# ReptileHeatMat-V1.net
KiCad netlist of a schematic drawn in EAGLE
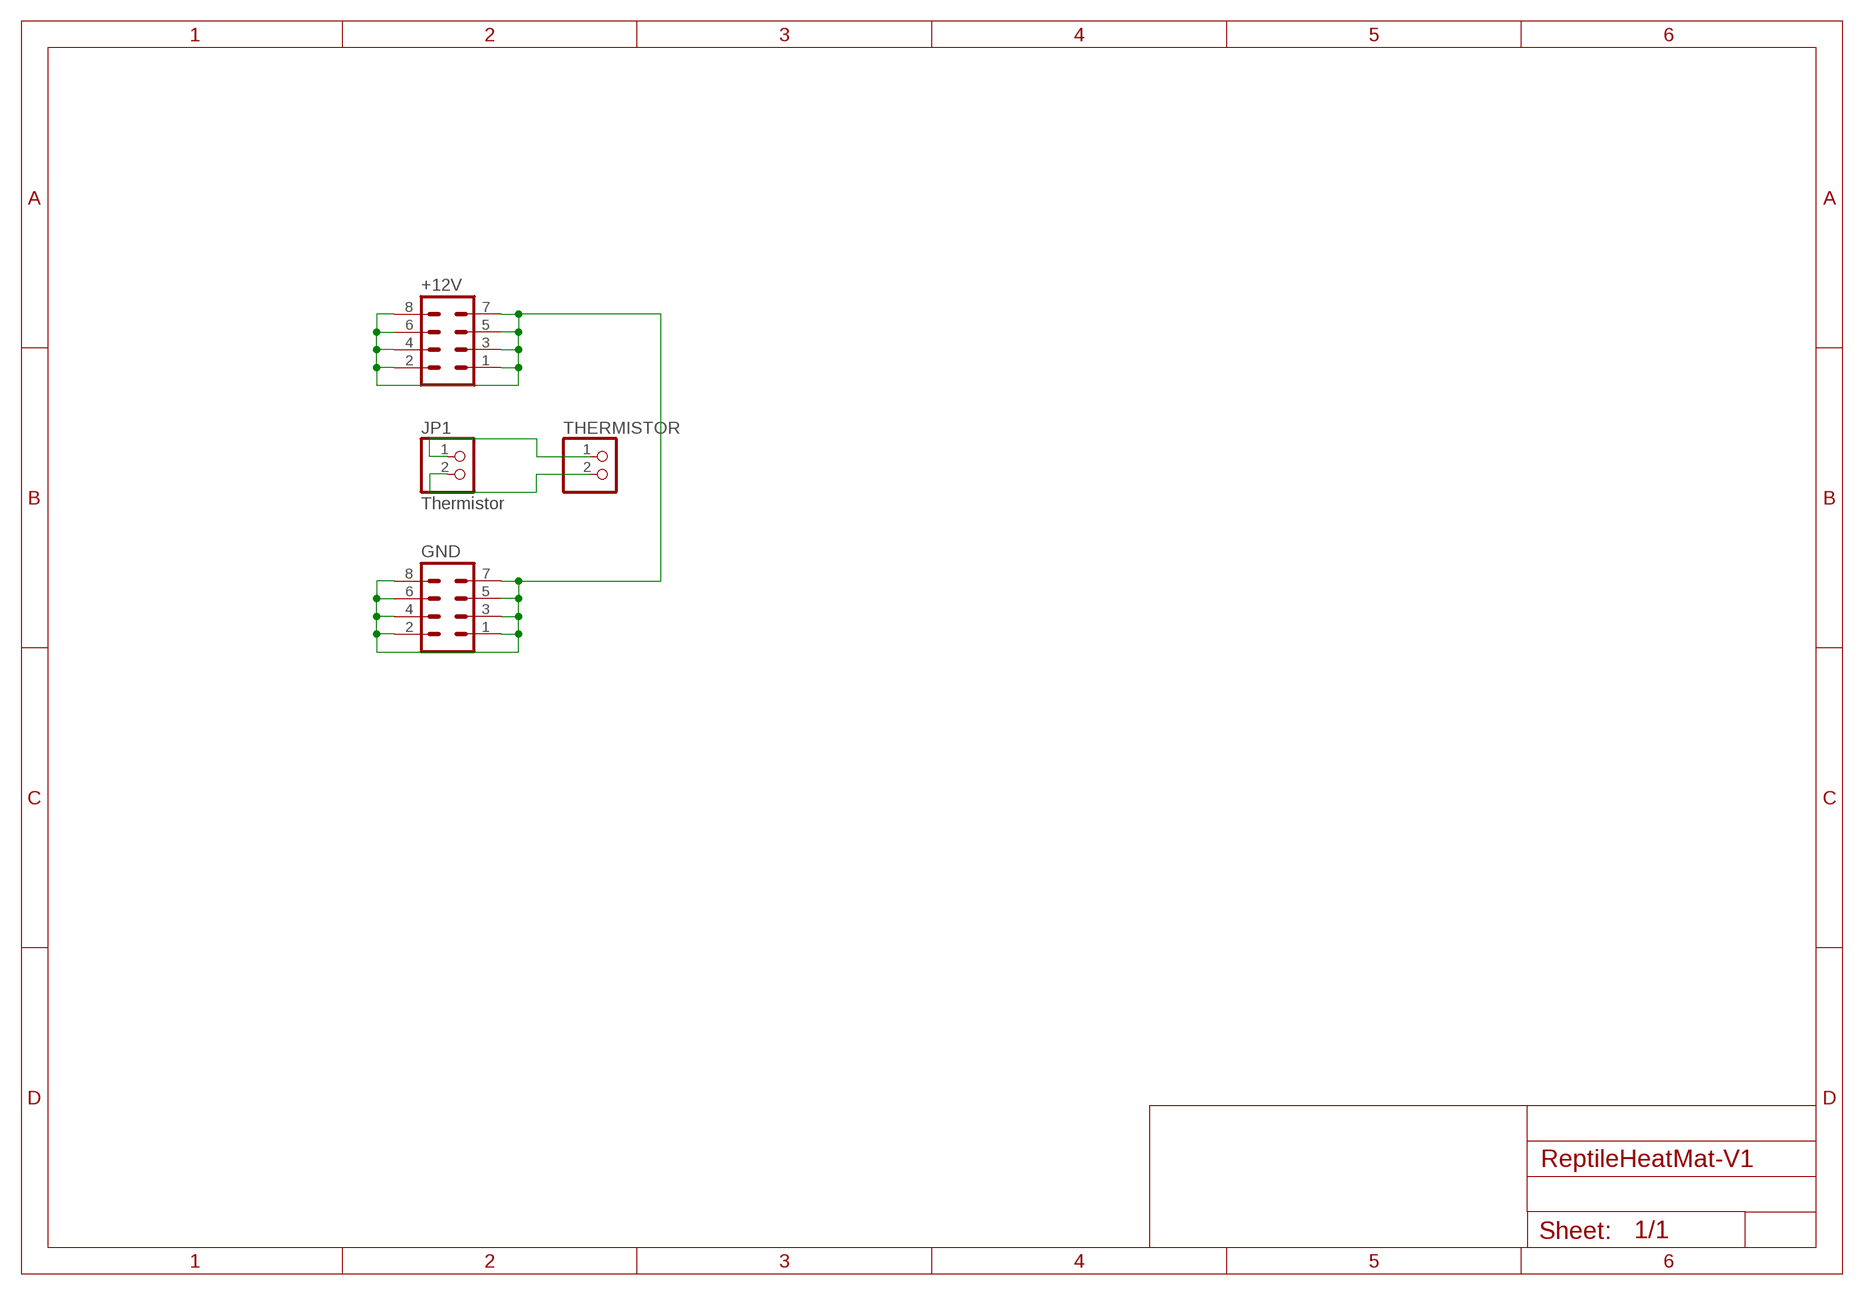
[diagram p0: schematic, sheet 1]

(export (version "E")
  (design (tool "Eeschema 10.0.6"))
  (components
    (comp (ref "+12V")
      (value "MA04-2")
      (footprint "eagle-import:MA04-2")
      (libsource (lib "eagle-import") (part "MA04-2"))
    )
    (comp (ref "GND")
      (value "MA04-2")
      (footprint "eagle-import:MA04-2")
      (libsource (lib "eagle-import") (part "MA04-2"))
    )
    (comp (ref "JP1")
      (value "Thermistor")
      (footprint "eagle-import:1X02")
      (libsource (lib "eagle-import") (part "PINHD-1X2"))
    )
    (comp (ref "THERMISTOR")
      (value "PINHD-1X2")
      (footprint "eagle-import:1X02")
      (libsource (lib "eagle-import") (part "PINHD-1X2"))
    )
  )
  (nets
    (net (code "1") (name "Net-(+12V-Pad1)") (class "Default")
      (node (ref "+12V") (pin "1") (pinfunction "1_1") (pintype "passive"))
      (node (ref "+12V") (pin "2") (pinfunction "2_2") (pintype "passive"))
      (node (ref "+12V") (pin "3") (pinfunction "3_3") (pintype "passive"))
      (node (ref "+12V") (pin "4") (pinfunction "4_4") (pintype "passive"))
      (node (ref "+12V") (pin "5") (pinfunction "5_5") (pintype "passive"))
      (node (ref "+12V") (pin "6") (pinfunction "6_6") (pintype "passive"))
      (node (ref "+12V") (pin "7") (pinfunction "7_7") (pintype "passive"))
      (node (ref "+12V") (pin "8") (pinfunction "8_8") (pintype "passive"))
      (node (ref "GND") (pin "1") (pinfunction "1_1") (pintype "passive"))
      (node (ref "GND") (pin "2") (pinfunction "2_2") (pintype "passive"))
      (node (ref "GND") (pin "3") (pinfunction "3_3") (pintype "passive"))
      (node (ref "GND") (pin "4") (pinfunction "4_4") (pintype "passive"))
      (node (ref "GND") (pin "5") (pinfunction "5_5") (pintype "passive"))
      (node (ref "GND") (pin "6") (pinfunction "6_6") (pintype "passive"))
      (node (ref "GND") (pin "7") (pinfunction "7_7") (pintype "passive"))
      (node (ref "GND") (pin "8") (pinfunction "8_8") (pintype "passive"))
    )
    (net (code "2") (name "Net-(JP1-Pad1)") (class "Default")
      (node (ref "JP1") (pin "1") (pinfunction "1_1") (pintype "passive"))
      (node (ref "THERMISTOR") (pin "1") (pinfunction "1_1") (pintype "passive"))
    )
    (net (code "3") (name "Net-(JP1-Pad2)") (class "Default")
      (node (ref "JP1") (pin "2") (pinfunction "2_2") (pintype "passive"))
      (node (ref "THERMISTOR") (pin "2") (pinfunction "2_2") (pintype "passive"))
    )
  )
)
